# uC.net
KiCad netlist of a schematic drawn in Altium Designer
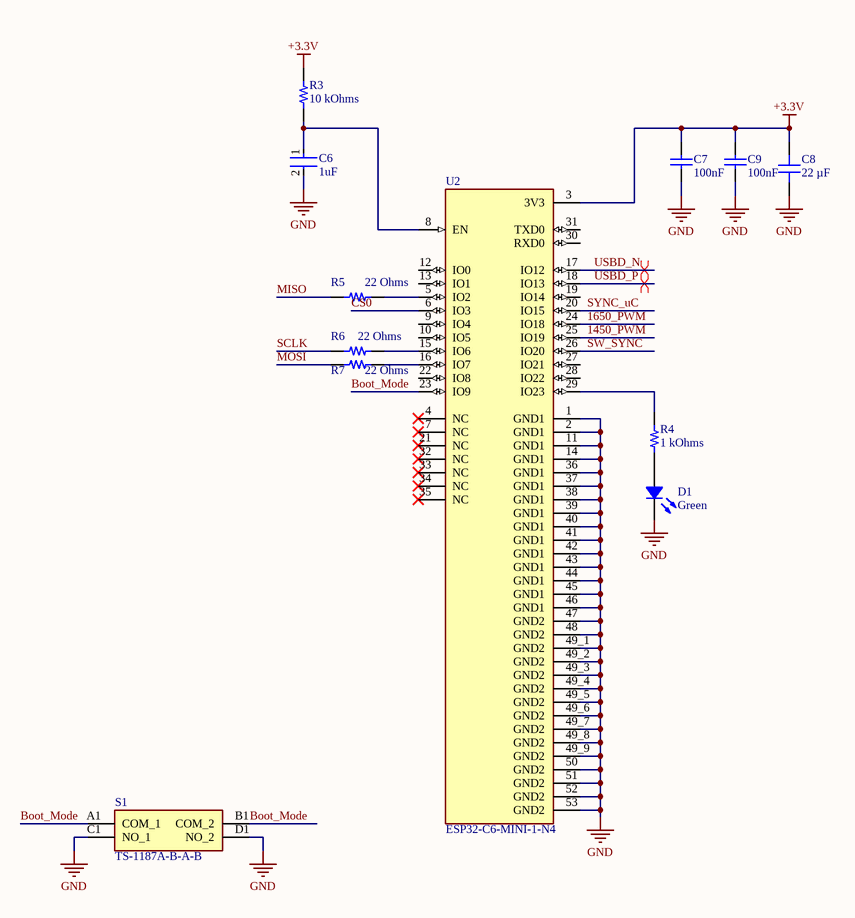
[diagram p0: uC.SchDoc]

(export (version "E")
  (design (tool "Eeschema 10.0.6"))
  (components
    (comp (ref "C6")
      (value "1uF")
      (footprint "FP-CL542-IPC_C")
      (description "Cap Ceramic 1uF 25V X5R ±10% SMD 0402 +85°C Paper T/R")
      (fields (field (name "TOLERANCE") "10%"))
      (libsource (lib "Altium Content Vault") (part "b4654b650e69147ec39a6b967a45e02"))
    )
    (comp (ref "C7")
      (value "100nF")
      (footprint "CAPC1050X55X23ML05T13")
      (description "Chip Capacitor, 100 nF, +/- 10%, 16 V, -55 to 125 degC, 0402 (1005 Metric), RoHS, Tape and Reel")
      (fields (field (name "MANUFACTURER") "Samsung Electro-Mechanics"))
      (libsource (lib "Altium Content Vault") (part "CAP-NP-2"))
    )
    (comp (ref "C8")
      (value "22 µF")
      (footprint "CAP 0603_1608")
      (description "CAP CER 22UF 6.3V X5R 0603")
      (fields
        (field (name "PART NUMBER") "CL10A226KQ8NRNE")
        (field (name "MANUFACTURER") "Samsung Electro-Mechanics")
      )
      (libsource (lib "Celestial Altium Library - altium_library") (part "Capacitor"))
    )
    (comp (ref "C9")
      (value "100nF")
      (footprint "CAPC1050X55X23ML05T13")
      (description "Chip Capacitor, 100 nF, +/- 10%, 16 V, -55 to 125 degC, 0402 (1005 Metric), RoHS, Tape and Reel")
      (fields (field (name "MANUFACTURER") "Samsung Electro-Mechanics"))
      (libsource (lib "Altium Content Vault") (part "CAP-NP-2"))
    )
    (comp (ref "D1")
      (value "Green")
      (footprint "LED 0805_2012 GREEN")
      (description "LED GREEN CLEAR 0805 SMD KT0805G")
      (fields (field (name "PART NUMBER") "SM0805GC") (field (name "MANUFACTURER") "Bivar Inc."))
      (libsource (lib "Celestial Altium Library - altium_library") (part "LED"))
    )
    (comp (ref "R3")
      (value "10 kOhms")
      (footprint "RES 0402_1005")
      (description "RES SMD 10K OHM 1% 1/16W 0402")
      (fields (field (name "PART NUMBER") "CRCW040210K0FKEE") (field (name "MANUFACTURER") "Vishay Dale"))
      (libsource (lib "Celestial Altium Library - altium_library") (part "Resistor"))
    )
    (comp (ref "R4")
      (value "1 kOhms")
      (footprint "RES 0402_1005")
      (description "RES SMD 1K OHM 0.1% 1/16W 0402")
      (fields
        (field (name "PART NUMBER") "CPF0402B1K0E")
        (field (name "MANUFACTURER") "TE Connectivity Passive Product")
      )
      (libsource (lib "Celestial Altium Library - altium_library") (part "Resistor"))
    )
    (comp (ref "R5")
      (value "22 Ohms")
      (footprint "RES 0402_1005")
      (description "RES SMD 22 OHM 0.5% 1/16W 0402")
      (fields (field (name "PART NUMBER") "RR0510R-220-D") (field (name "MANUFACTURER") "Susumu"))
      (libsource (lib "Celestial Altium Library - altium_library") (part "Resistor"))
    )
    (comp (ref "R6")
      (value "22 Ohms")
      (footprint "RES 0402_1005")
      (description "RES SMD 22 OHM 0.5% 1/16W 0402")
      (fields (field (name "PART NUMBER") "RR0510R-220-D") (field (name "MANUFACTURER") "Susumu"))
      (libsource (lib "Celestial Altium Library - altium_library") (part "Resistor"))
    )
    (comp (ref "R7")
      (value "22 Ohms")
      (footprint "RES 0402_1005")
      (description "RES SMD 22 OHM 0.5% 1/16W 0402")
      (fields (field (name "PART NUMBER") "RR0510R-220-D") (field (name "MANUFACTURER") "Susumu"))
      (libsource (lib "Celestial Altium Library - altium_library") (part "Resistor"))
    )
    (comp (ref "S1")
      (value "TS-1187A-B-A-B")
      (footprint "SamacSys:TS1187ABAB")
      (description "Switch")
      (libsource (lib "*") (part "TS-1187A-B-A-B"))
    )
    (comp (ref "U2")
      (value "ESP32-C6-MINI-1-N4")
      (footprint "XCVR_ESP32-C6-MINI-1-N4")
      (fields (field (name "MF") "Espressif Systems"))
      (libsource (lib "ESP32-C6-MINI-1-N4") (part "ESP32-C6-MINI-1-N4"))
    )
  )
  (nets
    (net (code "1") (name "+3.3V") (class "Default")
      (node (ref "C7") (pin "2") (pinfunction "2_2") (pintype "passive"))
      (node (ref "C8") (pin "2") (pinfunction "2_2") (pintype "passive"))
      (node (ref "C9") (pin "2") (pinfunction "2_2") (pintype "passive"))
      (node (ref "R3") (pin "2") (pinfunction "2_2") (pintype "passive"))
      (node (ref "U2") (pin "3") (pinfunction "3V3_3") (pintype "power_in"))
    )
    (net (code "2") (name "/1450_PWM") (class "Default")
      (node (ref "U2") (pin "25") (pinfunction "IO19_25") (pintype "bidirectional"))
    )
    (net (code "3") (name "/1650_PWM") (class "Default")
      (node (ref "U2") (pin "24") (pinfunction "IO18_24") (pintype "bidirectional"))
    )
    (net (code "4") (name "/Boot_Mode") (class "Default")
      (node (ref "S1") (pin "A1") (pinfunction "COM_1_A1") (pintype "passive"))
      (node (ref "S1") (pin "B1") (pinfunction "COM_2_B1") (pintype "passive"))
      (node (ref "U2") (pin "23") (pinfunction "IO9_23") (pintype "bidirectional"))
    )
    (net (code "5") (name "/CS0") (class "Default")
      (node (ref "U2") (pin "6") (pinfunction "IO3_6") (pintype "bidirectional"))
    )
    (net (code "6") (name "/MISO") (class "Default")
      (node (ref "R5") (pin "1") (pinfunction "1_1") (pintype "passive"))
    )
    (net (code "7") (name "/MOSI") (class "Default")
      (node (ref "R7") (pin "1") (pinfunction "1_1") (pintype "passive"))
    )
    (net (code "8") (name "/SCLK") (class "Default")
      (node (ref "R6") (pin "1") (pinfunction "1_1") (pintype "passive"))
    )
    (net (code "9") (name "/SW_SYNC") (class "Default")
      (node (ref "U2") (pin "26") (pinfunction "IO20_26") (pintype "bidirectional"))
    )
    (net (code "10") (name "/SYNC_uC") (class "Default")
      (node (ref "U2") (pin "20") (pinfunction "IO15_20") (pintype "bidirectional"))
    )
    (net (code "11") (name "/USBD_N") (class "Default")
      (node (ref "U2") (pin "17") (pinfunction "IO12_17") (pintype "bidirectional"))
    )
    (net (code "12") (name "/USBD_P") (class "Default")
      (node (ref "U2") (pin "18") (pinfunction "IO13_18") (pintype "bidirectional"))
    )
    (net (code "13") (name "GND") (class "Default")
      (node (ref "C6") (pin "2") (pinfunction "2_2") (pintype "passive"))
      (node (ref "C7") (pin "1") (pinfunction "1_1") (pintype "passive"))
      (node (ref "C8") (pin "1") (pinfunction "1_1") (pintype "passive"))
      (node (ref "C9") (pin "1") (pinfunction "1_1") (pintype "passive"))
      (node (ref "D1") (pin "2") (pinfunction "2_2") (pintype "passive"))
      (node (ref "S1") (pin "C1") (pinfunction "NO_1_C1") (pintype "passive"))
      (node (ref "S1") (pin "D1") (pinfunction "NO_2_D1") (pintype "passive"))
      (node (ref "U2") (pin "1") (pinfunction "GND1_1") (pintype "power_in"))
      (node (ref "U2") (pin "11") (pinfunction "GND1_11") (pintype "power_in"))
      (node (ref "U2") (pin "14") (pinfunction "GND1_14") (pintype "power_in"))
      (node (ref "U2") (pin "2") (pinfunction "GND1_2") (pintype "power_in"))
      (node (ref "U2") (pin "36") (pinfunction "GND1_36") (pintype "power_in"))
      (node (ref "U2") (pin "37") (pinfunction "GND1_37") (pintype "power_in"))
      (node (ref "U2") (pin "38") (pinfunction "GND1_38") (pintype "power_in"))
      (node (ref "U2") (pin "39") (pinfunction "GND1_39") (pintype "power_in"))
      (node (ref "U2") (pin "40") (pinfunction "GND1_40") (pintype "power_in"))
      (node (ref "U2") (pin "41") (pinfunction "GND1_41") (pintype "power_in"))
      (node (ref "U2") (pin "42") (pinfunction "GND1_42") (pintype "power_in"))
      (node (ref "U2") (pin "43") (pinfunction "GND1_43") (pintype "power_in"))
      (node (ref "U2") (pin "44") (pinfunction "GND1_44") (pintype "power_in"))
      (node (ref "U2") (pin "45") (pinfunction "GND1_45") (pintype "power_in"))
      (node (ref "U2") (pin "46") (pinfunction "GND1_46") (pintype "power_in"))
      (node (ref "U2") (pin "47") (pinfunction "GND2_47") (pintype "power_in"))
      (node (ref "U2") (pin "48") (pinfunction "GND2_48") (pintype "power_in"))
      (node (ref "U2") (pin "49_1") (pinfunction "GND2_49_1") (pintype "power_in"))
      (node (ref "U2") (pin "49_2") (pinfunction "GND2_49_2") (pintype "power_in"))
      (node (ref "U2") (pin "49_3") (pinfunction "GND2_49_3") (pintype "power_in"))
      (node (ref "U2") (pin "49_4") (pinfunction "GND2_49_4") (pintype "power_in"))
      (node (ref "U2") (pin "49_5") (pinfunction "GND2_49_5") (pintype "power_in"))
      (node (ref "U2") (pin "49_6") (pinfunction "GND2_49_6") (pintype "power_in"))
      (node (ref "U2") (pin "49_7") (pinfunction "GND2_49_7") (pintype "power_in"))
      (node (ref "U2") (pin "49_8") (pinfunction "GND2_49_8") (pintype "power_in"))
      (node (ref "U2") (pin "49_9") (pinfunction "GND2_49_9") (pintype "power_in"))
      (node (ref "U2") (pin "50") (pinfunction "GND2_50") (pintype "power_in"))
      (node (ref "U2") (pin "51") (pinfunction "GND2_51") (pintype "power_in"))
      (node (ref "U2") (pin "52") (pinfunction "GND2_52") (pintype "power_in"))
      (node (ref "U2") (pin "53") (pinfunction "GND2_53") (pintype "power_in"))
    )
    (net (code "14") (name "Net-(D1-Pad1)") (class "Default")
      (node (ref "D1") (pin "1") (pinfunction "1_1") (pintype "passive"))
      (node (ref "R4") (pin "1") (pinfunction "1_1") (pintype "passive"))
    )
    (net (code "15") (name "Net-(U2-EN)") (class "Default")
      (node (ref "C6") (pin "1") (pinfunction "1_1") (pintype "passive"))
      (node (ref "R3") (pin "1") (pinfunction "1_1") (pintype "passive"))
      (node (ref "U2") (pin "8") (pinfunction "EN_8") (pintype "input"))
    )
    (net (code "16") (name "Net-(U2-IO2)") (class "Default")
      (node (ref "R5") (pin "2") (pinfunction "2_2") (pintype "passive"))
      (node (ref "U2") (pin "5") (pinfunction "IO2_5") (pintype "bidirectional"))
    )
    (net (code "17") (name "Net-(U2-IO6)") (class "Default")
      (node (ref "R6") (pin "2") (pinfunction "2_2") (pintype "passive"))
      (node (ref "U2") (pin "15") (pinfunction "IO6_15") (pintype "bidirectional"))
    )
    (net (code "18") (name "Net-(U2-IO7)") (class "Default")
      (node (ref "R7") (pin "2") (pinfunction "2_2") (pintype "passive"))
      (node (ref "U2") (pin "16") (pinfunction "IO7_16") (pintype "bidirectional"))
    )
    (net (code "19") (name "Net-(U2-IO23)") (class "Default")
      (node (ref "R4") (pin "2") (pinfunction "2_2") (pintype "passive"))
      (node (ref "U2") (pin "29") (pinfunction "IO23_29") (pintype "bidirectional"))
    )
    (net (code "20") (name "unconnected-(U2-IO0-Pad12)") (class "Default")
      (node (ref "U2") (pin "12") (pinfunction "IO0_12") (pintype "bidirectional"))
    )
    (net (code "21") (name "unconnected-(U2-IO1-Pad13)") (class "Default")
      (node (ref "U2") (pin "13") (pinfunction "IO1_13") (pintype "bidirectional"))
    )
    (net (code "22") (name "unconnected-(U2-IO4-Pad9)") (class "Default")
      (node (ref "U2") (pin "9") (pinfunction "IO4_9") (pintype "bidirectional"))
    )
    (net (code "23") (name "unconnected-(U2-IO5-Pad10)") (class "Default")
      (node (ref "U2") (pin "10") (pinfunction "IO5_10") (pintype "bidirectional"))
    )
    (net (code "24") (name "unconnected-(U2-IO8-Pad22)") (class "Default")
      (node (ref "U2") (pin "22") (pinfunction "IO8_22") (pintype "bidirectional"))
    )
    (net (code "25") (name "unconnected-(U2-IO14-Pad19)") (class "Default")
      (node (ref "U2") (pin "19") (pinfunction "IO14_19") (pintype "bidirectional"))
    )
    (net (code "26") (name "unconnected-(U2-IO21-Pad27)") (class "Default")
      (node (ref "U2") (pin "27") (pinfunction "IO21_27") (pintype "bidirectional"))
    )
    (net (code "27") (name "unconnected-(U2-IO22-Pad28)") (class "Default")
      (node (ref "U2") (pin "28") (pinfunction "IO22_28") (pintype "bidirectional"))
    )
    (net (code "28") (name "unconnected-(U2-NC-Pad4)") (class "Default")
      (node (ref "U2") (pin "4") (pinfunction "NC_4") (pintype "passive+no_connect"))
    )
    (net (code "29") (name "unconnected-(U2-NC-Pad7)") (class "Default")
      (node (ref "U2") (pin "7") (pinfunction "NC_7") (pintype "passive+no_connect"))
    )
    (net (code "30") (name "unconnected-(U2-NC-Pad21)") (class "Default")
      (node (ref "U2") (pin "21") (pinfunction "NC_21") (pintype "passive+no_connect"))
    )
    (net (code "31") (name "unconnected-(U2-NC-Pad32)") (class "Default")
      (node (ref "U2") (pin "32") (pinfunction "NC_32") (pintype "passive+no_connect"))
    )
    (net (code "32") (name "unconnected-(U2-NC-Pad33)") (class "Default")
      (node (ref "U2") (pin "33") (pinfunction "NC_33") (pintype "passive+no_connect"))
    )
    (net (code "33") (name "unconnected-(U2-NC-Pad34)") (class "Default")
      (node (ref "U2") (pin "34") (pinfunction "NC_34") (pintype "passive+no_connect"))
    )
    (net (code "34") (name "unconnected-(U2-NC-Pad35)") (class "Default")
      (node (ref "U2") (pin "35") (pinfunction "NC_35") (pintype "passive+no_connect"))
    )
    (net (code "35") (name "unconnected-(U2-RXD0-Pad30)") (class "Default")
      (node (ref "U2") (pin "30") (pinfunction "RXD0_30") (pintype "bidirectional"))
    )
    (net (code "36") (name "unconnected-(U2-TXD0-Pad31)") (class "Default")
      (node (ref "U2") (pin "31") (pinfunction "TXD0_31") (pintype "bidirectional"))
    )
  )
)
